# BOT_Input_board_adi.net
KiCad netlist of a schematic drawn in EAGLE
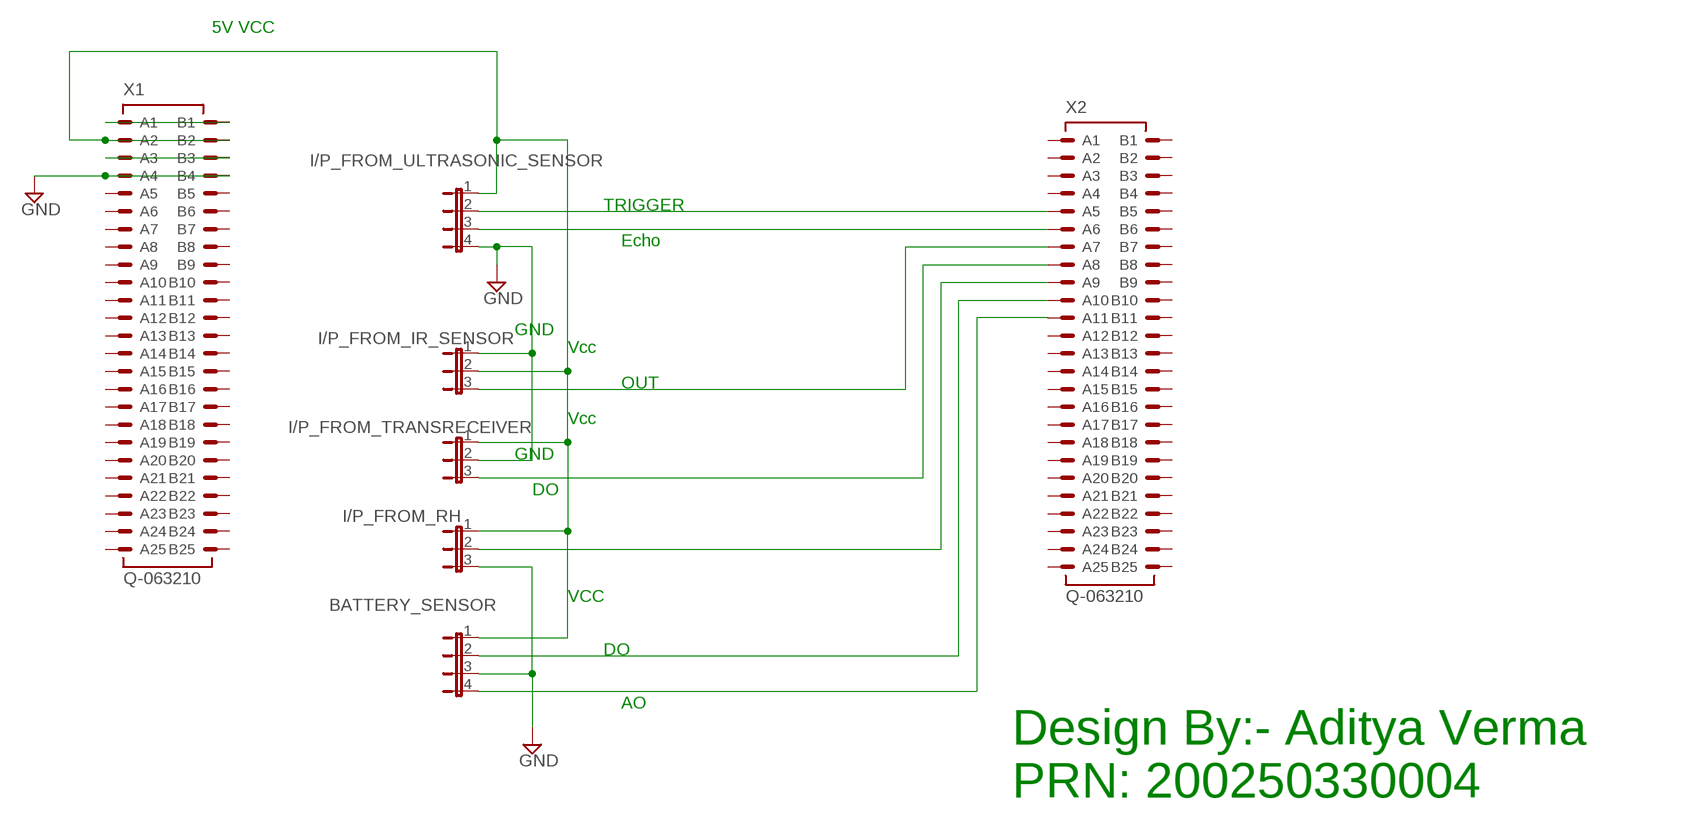
[diagram p0: schematic, sheet 1]

(export (version "E")
  (design (tool "Eeschema 10.0.6"))
  (components
    (comp (ref "BATTERY_SENSOR")
      (value "JP4E")
      (footprint "eagle-import:JP4")
      (libsource (lib "eagle-import") (part "JP4E"))
    )
    (comp (ref "I/P_FROM_IR_SENSOR")
      (value "JP2E")
      (footprint "eagle-import:JP2")
      (libsource (lib "eagle-import") (part "JP2E"))
    )
    (comp (ref "I/P_FROM_RH")
      (value "JP2E")
      (footprint "eagle-import:JP2")
      (libsource (lib "eagle-import") (part "JP2E"))
    )
    (comp (ref "I/P_FROM_TRANSRECEIVER")
      (value "JP2E")
      (footprint "eagle-import:JP2")
      (libsource (lib "eagle-import") (part "JP2E"))
    )
    (comp (ref "I/P_FROM_ULTRASONIC_SENSOR")
      (value "JP4E")
      (footprint "eagle-import:JP4")
      (libsource (lib "eagle-import") (part "JP4E"))
    )
    (comp (ref "X1")
      (value "Q-063210")
      (footprint "eagle-import:063210")
      (libsource (lib "eagle-import") (part "Q-063210"))
    )
    (comp (ref "X2")
      (value "Q-063210")
      (footprint "eagle-import:063210")
      (libsource (lib "eagle-import") (part "Q-063210"))
    )
  )
  (nets
    (net (code "1") (name "GND") (class "Default")
      (node (ref "BATTERY_SENSOR") (pin "3") (pinfunction "3_3") (pintype "passive"))
      (node (ref "I/P_FROM_IR_SENSOR") (pin "1") (pinfunction "1_1") (pintype "passive"))
      (node (ref "I/P_FROM_RH") (pin "3") (pinfunction "3_3") (pintype "passive"))
      (node (ref "I/P_FROM_TRANSRECEIVER") (pin "2") (pinfunction "2_2") (pintype "passive"))
      (node (ref "I/P_FROM_ULTRASONIC_SENSOR") (pin "4") (pinfunction "4_4") (pintype "passive"))
      (node (ref "X1") (pin "A4") (pinfunction "A4_A4") (pintype "passive"))
      (node (ref "X1") (pin "B4") (pinfunction "B4_B4") (pintype "passive"))
    )
    (net (code "2") (name "Net-(BATTERY_SENSOR-Pad1)") (class "Default")
      (node (ref "BATTERY_SENSOR") (pin "1") (pinfunction "1_1") (pintype "passive"))
      (node (ref "I/P_FROM_IR_SENSOR") (pin "2") (pinfunction "2_2") (pintype "passive"))
      (node (ref "I/P_FROM_RH") (pin "1") (pinfunction "1_1") (pintype "passive"))
      (node (ref "I/P_FROM_TRANSRECEIVER") (pin "1") (pinfunction "1_1") (pintype "passive"))
      (node (ref "I/P_FROM_ULTRASONIC_SENSOR") (pin "1") (pinfunction "1_1") (pintype "passive"))
      (node (ref "X1") (pin "A2") (pinfunction "A2_A2") (pintype "passive"))
      (node (ref "X1") (pin "B2") (pinfunction "B2_B2") (pintype "passive"))
    )
    (net (code "3") (name "Net-(BATTERY_SENSOR-Pad2)") (class "Default")
      (node (ref "BATTERY_SENSOR") (pin "2") (pinfunction "2_2") (pintype "passive"))
      (node (ref "X2") (pin "A10") (pinfunction "A10_A10") (pintype "passive"))
    )
    (net (code "4") (name "Net-(BATTERY_SENSOR-Pad4)") (class "Default")
      (node (ref "BATTERY_SENSOR") (pin "4") (pinfunction "4_4") (pintype "passive"))
      (node (ref "X2") (pin "A11") (pinfunction "A11_A11") (pintype "passive"))
    )
    (net (code "5") (name "Net-(I/P_FROM_IR_SENSOR-Pad3)") (class "Default")
      (node (ref "I/P_FROM_IR_SENSOR") (pin "3") (pinfunction "3_3") (pintype "passive"))
      (node (ref "X2") (pin "A7") (pinfunction "A7_A7") (pintype "passive"))
    )
    (net (code "6") (name "Net-(I/P_FROM_RH-Pad2)") (class "Default")
      (node (ref "I/P_FROM_RH") (pin "2") (pinfunction "2_2") (pintype "passive"))
      (node (ref "X2") (pin "A9") (pinfunction "A9_A9") (pintype "passive"))
    )
    (net (code "7") (name "Net-(I/P_FROM_TRANSRECEIVER-Pad3)") (class "Default")
      (node (ref "I/P_FROM_TRANSRECEIVER") (pin "3") (pinfunction "3_3") (pintype "passive"))
      (node (ref "X2") (pin "A8") (pinfunction "A8_A8") (pintype "passive"))
    )
    (net (code "8") (name "Net-(I/P_FROM_ULTRASONIC_SENSOR-Pad2)") (class "Default")
      (node (ref "I/P_FROM_ULTRASONIC_SENSOR") (pin "2") (pinfunction "2_2") (pintype "passive"))
      (node (ref "X2") (pin "A5") (pinfunction "A5_A5") (pintype "passive"))
    )
    (net (code "9") (name "Net-(I/P_FROM_ULTRASONIC_SENSOR-Pad3)") (class "Default")
      (node (ref "I/P_FROM_ULTRASONIC_SENSOR") (pin "3") (pinfunction "3_3") (pintype "passive"))
      (node (ref "X2") (pin "A6") (pinfunction "A6_A6") (pintype "passive"))
    )
    (net (code "10") (name "Net-(X1-PadA1)") (class "Default")
      (node (ref "X1") (pin "A1") (pinfunction "A1_A1") (pintype "passive"))
      (node (ref "X1") (pin "B1") (pinfunction "B1_B1") (pintype "passive"))
    )
    (net (code "11") (name "Net-(X1-PadA3)") (class "Default")
      (node (ref "X1") (pin "A3") (pinfunction "A3_A3") (pintype "passive"))
      (node (ref "X1") (pin "B3") (pinfunction "B3_B3") (pintype "passive"))
    )
    (net (code "12") (name "unconnected-(X1-PadA5)") (class "Default")
      (node (ref "X1") (pin "A5") (pinfunction "A5_A5") (pintype "passive"))
    )
    (net (code "13") (name "unconnected-(X1-PadA6)") (class "Default")
      (node (ref "X1") (pin "A6") (pinfunction "A6_A6") (pintype "passive"))
    )
    (net (code "14") (name "unconnected-(X1-PadA7)") (class "Default")
      (node (ref "X1") (pin "A7") (pinfunction "A7_A7") (pintype "passive"))
    )
    (net (code "15") (name "unconnected-(X1-PadA8)") (class "Default")
      (node (ref "X1") (pin "A8") (pinfunction "A8_A8") (pintype "passive"))
    )
    (net (code "16") (name "unconnected-(X1-PadA9)") (class "Default")
      (node (ref "X1") (pin "A9") (pinfunction "A9_A9") (pintype "passive"))
    )
    (net (code "17") (name "unconnected-(X1-PadA10)") (class "Default")
      (node (ref "X1") (pin "A10") (pinfunction "A10_A10") (pintype "passive"))
    )
    (net (code "18") (name "unconnected-(X1-PadA11)") (class "Default")
      (node (ref "X1") (pin "A11") (pinfunction "A11_A11") (pintype "passive"))
    )
    (net (code "19") (name "unconnected-(X1-PadA12)") (class "Default")
      (node (ref "X1") (pin "A12") (pinfunction "A12_A12") (pintype "passive"))
    )
    (net (code "20") (name "unconnected-(X1-PadA13)") (class "Default")
      (node (ref "X1") (pin "A13") (pinfunction "A13_A13") (pintype "passive"))
    )
    (net (code "21") (name "unconnected-(X1-PadA14)") (class "Default")
      (node (ref "X1") (pin "A14") (pinfunction "A14_A14") (pintype "passive"))
    )
    (net (code "22") (name "unconnected-(X1-PadA15)") (class "Default")
      (node (ref "X1") (pin "A15") (pinfunction "A15_A15") (pintype "passive"))
    )
    (net (code "23") (name "unconnected-(X1-PadA16)") (class "Default")
      (node (ref "X1") (pin "A16") (pinfunction "A16_A16") (pintype "passive"))
    )
    (net (code "24") (name "unconnected-(X1-PadA17)") (class "Default")
      (node (ref "X1") (pin "A17") (pinfunction "A17_A17") (pintype "passive"))
    )
    (net (code "25") (name "unconnected-(X1-PadA18)") (class "Default")
      (node (ref "X1") (pin "A18") (pinfunction "A18_A18") (pintype "passive"))
    )
    (net (code "26") (name "unconnected-(X1-PadA19)") (class "Default")
      (node (ref "X1") (pin "A19") (pinfunction "A19_A19") (pintype "passive"))
    )
    (net (code "27") (name "unconnected-(X1-PadA20)") (class "Default")
      (node (ref "X1") (pin "A20") (pinfunction "A20_A20") (pintype "passive"))
    )
    (net (code "28") (name "unconnected-(X1-PadA21)") (class "Default")
      (node (ref "X1") (pin "A21") (pinfunction "A21_A21") (pintype "passive"))
    )
    (net (code "29") (name "unconnected-(X1-PadA22)") (class "Default")
      (node (ref "X1") (pin "A22") (pinfunction "A22_A22") (pintype "passive"))
    )
    (net (code "30") (name "unconnected-(X1-PadA23)") (class "Default")
      (node (ref "X1") (pin "A23") (pinfunction "A23_A23") (pintype "passive"))
    )
    (net (code "31") (name "unconnected-(X1-PadA24)") (class "Default")
      (node (ref "X1") (pin "A24") (pinfunction "A24_A24") (pintype "passive"))
    )
    (net (code "32") (name "unconnected-(X1-PadA25)") (class "Default")
      (node (ref "X1") (pin "A25") (pinfunction "A25_A25") (pintype "passive"))
    )
    (net (code "33") (name "unconnected-(X1-PadB5)") (class "Default")
      (node (ref "X1") (pin "B5") (pinfunction "B5_B5") (pintype "passive"))
    )
    (net (code "34") (name "unconnected-(X1-PadB6)") (class "Default")
      (node (ref "X1") (pin "B6") (pinfunction "B6_B6") (pintype "passive"))
    )
    (net (code "35") (name "unconnected-(X1-PadB7)") (class "Default")
      (node (ref "X1") (pin "B7") (pinfunction "B7_B7") (pintype "passive"))
    )
    (net (code "36") (name "unconnected-(X1-PadB8)") (class "Default")
      (node (ref "X1") (pin "B8") (pinfunction "B8_B8") (pintype "passive"))
    )
    (net (code "37") (name "unconnected-(X1-PadB9)") (class "Default")
      (node (ref "X1") (pin "B9") (pinfunction "B9_B9") (pintype "passive"))
    )
    (net (code "38") (name "unconnected-(X1-PadB10)") (class "Default")
      (node (ref "X1") (pin "B10") (pinfunction "B10_B10") (pintype "passive"))
    )
    (net (code "39") (name "unconnected-(X1-PadB11)") (class "Default")
      (node (ref "X1") (pin "B11") (pinfunction "B11_B11") (pintype "passive"))
    )
    (net (code "40") (name "unconnected-(X1-PadB12)") (class "Default")
      (node (ref "X1") (pin "B12") (pinfunction "B12_B12") (pintype "passive"))
    )
    (net (code "41") (name "unconnected-(X1-PadB13)") (class "Default")
      (node (ref "X1") (pin "B13") (pinfunction "B13_B13") (pintype "passive"))
    )
    (net (code "42") (name "unconnected-(X1-PadB14)") (class "Default")
      (node (ref "X1") (pin "B14") (pinfunction "B14_B14") (pintype "passive"))
    )
    (net (code "43") (name "unconnected-(X1-PadB15)") (class "Default")
      (node (ref "X1") (pin "B15") (pinfunction "B15_B15") (pintype "passive"))
    )
    (net (code "44") (name "unconnected-(X1-PadB16)") (class "Default")
      (node (ref "X1") (pin "B16") (pinfunction "B16_B16") (pintype "passive"))
    )
    (net (code "45") (name "unconnected-(X1-PadB17)") (class "Default")
      (node (ref "X1") (pin "B17") (pinfunction "B17_B17") (pintype "passive"))
    )
    (net (code "46") (name "unconnected-(X1-PadB18)") (class "Default")
      (node (ref "X1") (pin "B18") (pinfunction "B18_B18") (pintype "passive"))
    )
    (net (code "47") (name "unconnected-(X1-PadB19)") (class "Default")
      (node (ref "X1") (pin "B19") (pinfunction "B19_B19") (pintype "passive"))
    )
    (net (code "48") (name "unconnected-(X1-PadB20)") (class "Default")
      (node (ref "X1") (pin "B20") (pinfunction "B20_B20") (pintype "passive"))
    )
    (net (code "49") (name "unconnected-(X1-PadB21)") (class "Default")
      (node (ref "X1") (pin "B21") (pinfunction "B21_B21") (pintype "passive"))
    )
    (net (code "50") (name "unconnected-(X1-PadB22)") (class "Default")
      (node (ref "X1") (pin "B22") (pinfunction "B22_B22") (pintype "passive"))
    )
    (net (code "51") (name "unconnected-(X1-PadB23)") (class "Default")
      (node (ref "X1") (pin "B23") (pinfunction "B23_B23") (pintype "passive"))
    )
    (net (code "52") (name "unconnected-(X1-PadB24)") (class "Default")
      (node (ref "X1") (pin "B24") (pinfunction "B24_B24") (pintype "passive"))
    )
    (net (code "53") (name "unconnected-(X1-PadB25)") (class "Default")
      (node (ref "X1") (pin "B25") (pinfunction "B25_B25") (pintype "passive"))
    )
    (net (code "54") (name "unconnected-(X2-PadA1)") (class "Default")
      (node (ref "X2") (pin "A1") (pinfunction "A1_A1") (pintype "passive"))
    )
    (net (code "55") (name "unconnected-(X2-PadA2)") (class "Default")
      (node (ref "X2") (pin "A2") (pinfunction "A2_A2") (pintype "passive"))
    )
    (net (code "56") (name "unconnected-(X2-PadA3)") (class "Default")
      (node (ref "X2") (pin "A3") (pinfunction "A3_A3") (pintype "passive"))
    )
    (net (code "57") (name "unconnected-(X2-PadA4)") (class "Default")
      (node (ref "X2") (pin "A4") (pinfunction "A4_A4") (pintype "passive"))
    )
    (net (code "58") (name "unconnected-(X2-PadA12)") (class "Default")
      (node (ref "X2") (pin "A12") (pinfunction "A12_A12") (pintype "passive"))
    )
    (net (code "59") (name "unconnected-(X2-PadA13)") (class "Default")
      (node (ref "X2") (pin "A13") (pinfunction "A13_A13") (pintype "passive"))
    )
    (net (code "60") (name "unconnected-(X2-PadA14)") (class "Default")
      (node (ref "X2") (pin "A14") (pinfunction "A14_A14") (pintype "passive"))
    )
    (net (code "61") (name "unconnected-(X2-PadA15)") (class "Default")
      (node (ref "X2") (pin "A15") (pinfunction "A15_A15") (pintype "passive"))
    )
    (net (code "62") (name "unconnected-(X2-PadA16)") (class "Default")
      (node (ref "X2") (pin "A16") (pinfunction "A16_A16") (pintype "passive"))
    )
    (net (code "63") (name "unconnected-(X2-PadA17)") (class "Default")
      (node (ref "X2") (pin "A17") (pinfunction "A17_A17") (pintype "passive"))
    )
    (net (code "64") (name "unconnected-(X2-PadA18)") (class "Default")
      (node (ref "X2") (pin "A18") (pinfunction "A18_A18") (pintype "passive"))
    )
    (net (code "65") (name "unconnected-(X2-PadA19)") (class "Default")
      (node (ref "X2") (pin "A19") (pinfunction "A19_A19") (pintype "passive"))
    )
    (net (code "66") (name "unconnected-(X2-PadA20)") (class "Default")
      (node (ref "X2") (pin "A20") (pinfunction "A20_A20") (pintype "passive"))
    )
    (net (code "67") (name "unconnected-(X2-PadA21)") (class "Default")
      (node (ref "X2") (pin "A21") (pinfunction "A21_A21") (pintype "passive"))
    )
    (net (code "68") (name "unconnected-(X2-PadA22)") (class "Default")
      (node (ref "X2") (pin "A22") (pinfunction "A22_A22") (pintype "passive"))
    )
    (net (code "69") (name "unconnected-(X2-PadA23)") (class "Default")
      (node (ref "X2") (pin "A23") (pinfunction "A23_A23") (pintype "passive"))
    )
    (net (code "70") (name "unconnected-(X2-PadA24)") (class "Default")
      (node (ref "X2") (pin "A24") (pinfunction "A24_A24") (pintype "passive"))
    )
    (net (code "71") (name "unconnected-(X2-PadA25)") (class "Default")
      (node (ref "X2") (pin "A25") (pinfunction "A25_A25") (pintype "passive"))
    )
    (net (code "72") (name "unconnected-(X2-PadB1)") (class "Default")
      (node (ref "X2") (pin "B1") (pinfunction "B1_B1") (pintype "passive"))
    )
    (net (code "73") (name "unconnected-(X2-PadB2)") (class "Default")
      (node (ref "X2") (pin "B2") (pinfunction "B2_B2") (pintype "passive"))
    )
    (net (code "74") (name "unconnected-(X2-PadB3)") (class "Default")
      (node (ref "X2") (pin "B3") (pinfunction "B3_B3") (pintype "passive"))
    )
    (net (code "75") (name "unconnected-(X2-PadB4)") (class "Default")
      (node (ref "X2") (pin "B4") (pinfunction "B4_B4") (pintype "passive"))
    )
    (net (code "76") (name "unconnected-(X2-PadB5)") (class "Default")
      (node (ref "X2") (pin "B5") (pinfunction "B5_B5") (pintype "passive"))
    )
    (net (code "77") (name "unconnected-(X2-PadB6)") (class "Default")
      (node (ref "X2") (pin "B6") (pinfunction "B6_B6") (pintype "passive"))
    )
    (net (code "78") (name "unconnected-(X2-PadB7)") (class "Default")
      (node (ref "X2") (pin "B7") (pinfunction "B7_B7") (pintype "passive"))
    )
    (net (code "79") (name "unconnected-(X2-PadB8)") (class "Default")
      (node (ref "X2") (pin "B8") (pinfunction "B8_B8") (pintype "passive"))
    )
    (net (code "80") (name "unconnected-(X2-PadB9)") (class "Default")
      (node (ref "X2") (pin "B9") (pinfunction "B9_B9") (pintype "passive"))
    )
    (net (code "81") (name "unconnected-(X2-PadB10)") (class "Default")
      (node (ref "X2") (pin "B10") (pinfunction "B10_B10") (pintype "passive"))
    )
    (net (code "82") (name "unconnected-(X2-PadB11)") (class "Default")
      (node (ref "X2") (pin "B11") (pinfunction "B11_B11") (pintype "passive"))
    )
    (net (code "83") (name "unconnected-(X2-PadB12)") (class "Default")
      (node (ref "X2") (pin "B12") (pinfunction "B12_B12") (pintype "passive"))
    )
    (net (code "84") (name "unconnected-(X2-PadB13)") (class "Default")
      (node (ref "X2") (pin "B13") (pinfunction "B13_B13") (pintype "passive"))
    )
    (net (code "85") (name "unconnected-(X2-PadB14)") (class "Default")
      (node (ref "X2") (pin "B14") (pinfunction "B14_B14") (pintype "passive"))
    )
    (net (code "86") (name "unconnected-(X2-PadB15)") (class "Default")
      (node (ref "X2") (pin "B15") (pinfunction "B15_B15") (pintype "passive"))
    )
    (net (code "87") (name "unconnected-(X2-PadB16)") (class "Default")
      (node (ref "X2") (pin "B16") (pinfunction "B16_B16") (pintype "passive"))
    )
    (net (code "88") (name "unconnected-(X2-PadB17)") (class "Default")
      (node (ref "X2") (pin "B17") (pinfunction "B17_B17") (pintype "passive"))
    )
    (net (code "89") (name "unconnected-(X2-PadB18)") (class "Default")
      (node (ref "X2") (pin "B18") (pinfunction "B18_B18") (pintype "passive"))
    )
    (net (code "90") (name "unconnected-(X2-PadB19)") (class "Default")
      (node (ref "X2") (pin "B19") (pinfunction "B19_B19") (pintype "passive"))
    )
    (net (code "91") (name "unconnected-(X2-PadB20)") (class "Default")
      (node (ref "X2") (pin "B20") (pinfunction "B20_B20") (pintype "passive"))
    )
    (net (code "92") (name "unconnected-(X2-PadB21)") (class "Default")
      (node (ref "X2") (pin "B21") (pinfunction "B21_B21") (pintype "passive"))
    )
    (net (code "93") (name "unconnected-(X2-PadB22)") (class "Default")
      (node (ref "X2") (pin "B22") (pinfunction "B22_B22") (pintype "passive"))
    )
    (net (code "94") (name "unconnected-(X2-PadB23)") (class "Default")
      (node (ref "X2") (pin "B23") (pinfunction "B23_B23") (pintype "passive"))
    )
    (net (code "95") (name "unconnected-(X2-PadB24)") (class "Default")
      (node (ref "X2") (pin "B24") (pinfunction "B24_B24") (pintype "passive"))
    )
    (net (code "96") (name "unconnected-(X2-PadB25)") (class "Default")
      (node (ref "X2") (pin "B25") (pinfunction "B25_B25") (pintype "passive"))
    )
  )
)
